# larduino.net
KiCad netlist of a schematic drawn in Altium Designer
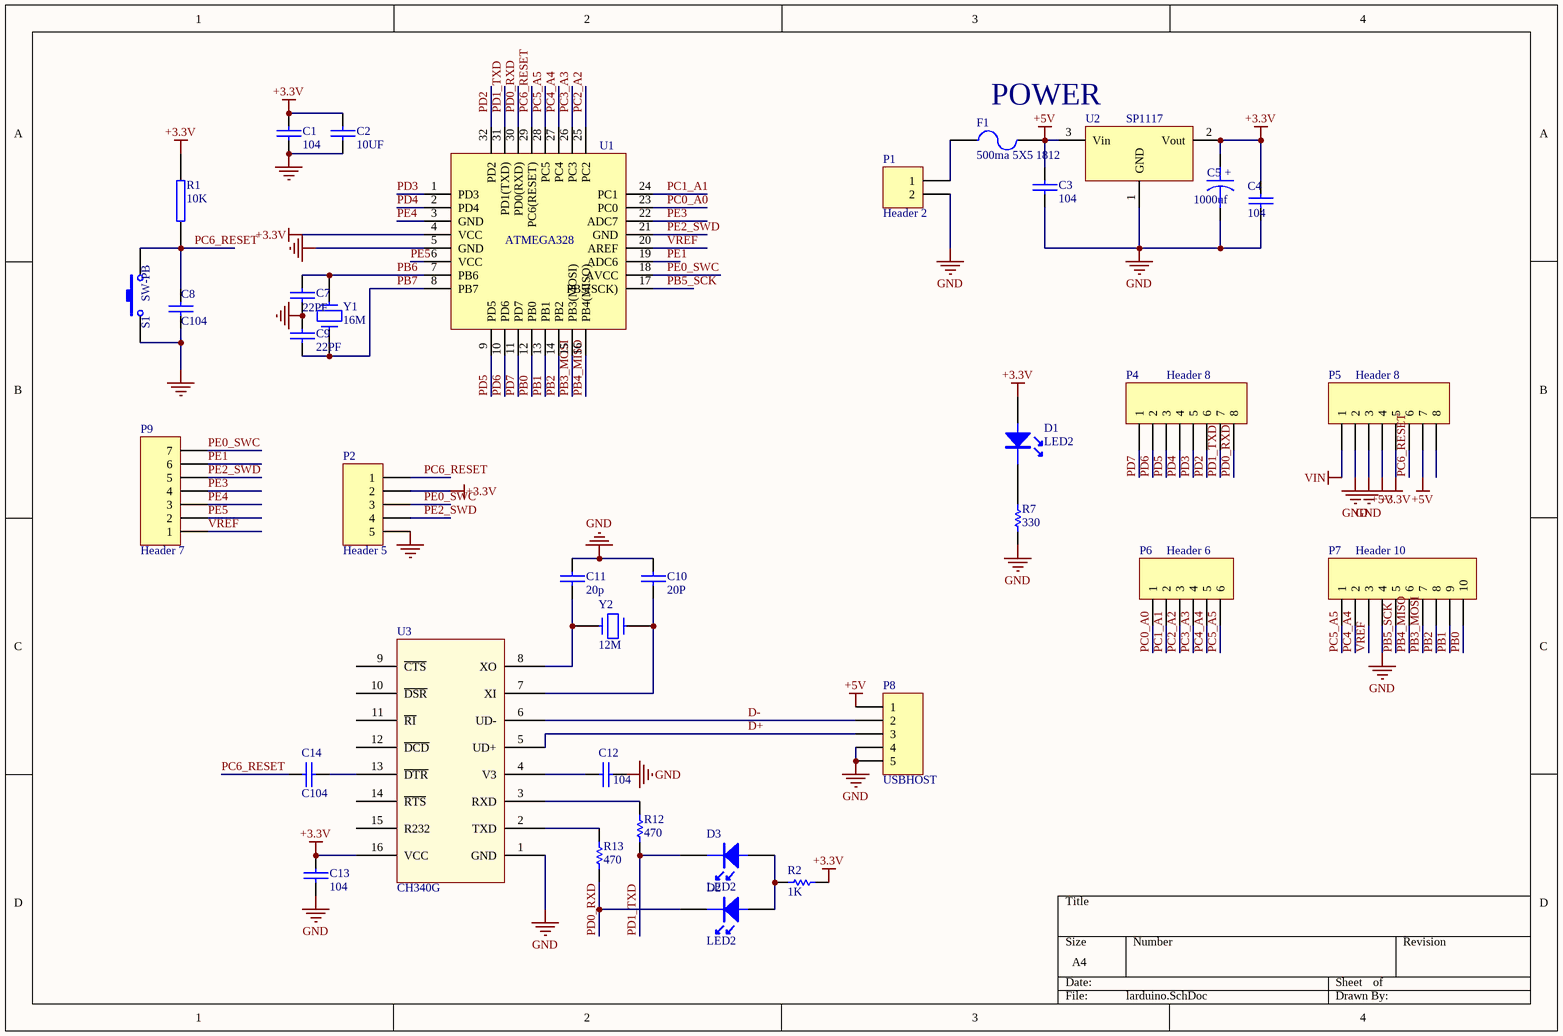
[diagram p0: larduino.SchDoc]

(export (version "E")
  (design (tool "Eeschema 10.0.6"))
  (components
    (comp (ref "C1")
      (value "104")
      (footprint "0805C1")
      (description "Capacitor")
      (libsource (lib "*") (part "CAP"))
    )
    (comp (ref "C2")
      (value "10UF")
      (footprint "0805C1")
      (description "Capacitor")
      (libsource (lib "*") (part "CAP"))
    )
    (comp (ref "C3")
      (value "104")
      (footprint "0805C1")
      (description "Capacitor")
      (libsource (lib "*") (part "CAP"))
    )
    (comp (ref "C4")
      (value "104")
      (footprint "0805C1")
      (description "Capacitor")
      (libsource (lib "*") (part "CAP"))
    )
    (comp (ref "C5")
      (value "1000uf")
      (footprint "c6.3*5.3")
      (description "Capacitor")
      (libsource (lib "*") (part "CAPACITOR POL"))
    )
    (comp (ref "C7")
      (value "22PF")
      (footprint "0805C1")
      (description "Capacitor")
      (libsource (lib "*") (part "CAP"))
    )
    (comp (ref "C8")
      (value "C104")
      (footprint "0805C1")
      (description "Capacitor")
      (libsource (lib "*") (part "CAP"))
    )
    (comp (ref "C9")
      (value "22PF")
      (footprint "0805C1")
      (description "Capacitor")
      (libsource (lib "*") (part "CAP"))
    )
    (comp (ref "C10")
      (value "20P")
      (footprint "0805C1")
      (description "Capacitor")
      (libsource (lib "*") (part "CAP"))
    )
    (comp (ref "C11")
      (value "20p")
      (footprint "0805C1")
      (description "Capacitor")
      (libsource (lib "*") (part "CAP"))
    )
    (comp (ref "C12")
      (value "104")
      (footprint "0805C1")
      (description "Capacitor")
      (libsource (lib "*") (part "CAP"))
    )
    (comp (ref "C13")
      (value "104")
      (footprint "0805C1")
      (description "Capacitor")
      (libsource (lib "*") (part "CAP"))
    )
    (comp (ref "C14")
      (value "C104")
      (footprint "0805C1")
      (description "Capacitor")
      (libsource (lib "*") (part "CAP"))
    )
    (comp (ref "D1") (value "LED2") (footprint "0805LED") (libsource (lib "*") (part "LED")))
    (comp (ref "D2") (value "LED2") (footprint "0805LED") (libsource (lib "*") (part "LED")))
    (comp (ref "D3") (value "LED2") (footprint "0805LED") (libsource (lib "*") (part "LED")))
    (comp (ref "F1")
      (value "500ma 5X5 1812")
      (footprint "1812R")
      (description "Fuse")
      (fields (field (name "PUBLISHER") "Altium Limited"))
      (libsource (lib "Miscellaneous Devices") (part "Fuse 2"))
    )
    (comp (ref "P1")
      (value "Header 2")
      (footprint "5VINPUT")
      (description "Header, 2-Pin")
      (fields (field (name "PUBLISHER") "Altium Limited"))
      (libsource (lib "Miscellaneous Connectors") (part "Header 2"))
    )
    (comp (ref "P2")
      (value "Header 5")
      (footprint "HDR1X5")
      (description "Header, 5-Pin")
      (fields (field (name "PUBLISHER") "Altium Limited"))
      (libsource (lib "") (part "Header 5_1"))
    )
    (comp (ref "P4")
      (value "Header 8")
      (footprint "HDR1X8")
      (description "Header, 8-Pin")
      (fields (field (name "PUBLISHER") "Altium Limited"))
      (libsource (lib "Miscellaneous Connectors") (part "Header 8"))
    )
    (comp (ref "P5")
      (value "Header 8")
      (footprint "HDR1X8")
      (description "Header, 8-Pin")
      (fields (field (name "PUBLISHER") "Altium Limited"))
      (libsource (lib "Miscellaneous Connectors") (part "Header 8"))
    )
    (comp (ref "P6")
      (value "Header 6")
      (footprint "HDR1X6")
      (description "Header, 6-Pin")
      (fields (field (name "PUBLISHER") "Altium Limited"))
      (libsource (lib "Miscellaneous Connectors") (part "Header 6"))
    )
    (comp (ref "P7")
      (value "Header 10")
      (footprint "HDR1X10")
      (description "Header, 10-Pin")
      (fields (field (name "PUBLISHER") "Altium Limited"))
      (libsource (lib "Miscellaneous Connectors") (part "Header 10"))
    )
    (comp (ref "P8")
      (value "USBHOST")
      (footprint "USB_mini")
      (description "Header, 5-Pin")
      (fields (field (name "PUBLISHER") "Altium Limited"))
      (libsource (lib "Miscellaneous Connectors") (part "Header 5"))
    )
    (comp (ref "P9")
      (value "Header 7")
      (footprint "HDR1X7")
      (description "Header, 7-Pin")
      (fields (field (name "PUBLISHER") "Altium Limited"))
      (libsource (lib "Miscellaneous Connectors") (part "Header 7"))
    )
    (comp (ref "R1") (value "10K") (footprint "0805R1") (libsource (lib "*") (part "RES2")))
    (comp (ref "R2")
      (value "1K")
      (footprint "0805R1")
      (description "Semiconductor Resistor")
      (fields (field (name "Comment") "Res Semi") (field (name "PUBLISHER") "Altium Limited"))
      (libsource (lib "Miscellaneous Devices") (part "Res Semi"))
    )
    (comp (ref "R7")
      (value "330")
      (footprint "0805R1")
      (description "Resistor")
      (fields (field (name "Comment") "Res1") (field (name "PUBLISHER") "Altium Limited"))
      (libsource (lib "Miscellaneous Devices") (part "Res1"))
    )
    (comp (ref "R12")
      (value "470")
      (footprint "0805R1")
      (description "Semiconductor Resistor")
      (fields (field (name "Comment") "Res Semi") (field (name "PUBLISHER") "Altium Limited"))
      (libsource (lib "Miscellaneous Devices") (part "Res Semi"))
    )
    (comp (ref "R13")
      (value "470")
      (footprint "0805R1")
      (description "Semiconductor Resistor")
      (fields (field (name "Comment") "Res Semi") (field (name "PUBLISHER") "Altium Limited"))
      (libsource (lib "Miscellaneous Devices") (part "Res Semi"))
    )
    (comp (ref "S1")
      (value "SW-PB")
      (footprint "KEY_6*6*X _SMT")
      (description "Switch")
      (fields (field (name "PUBLISHER") "Altium Limited"))
      (libsource (lib "Miscellaneous Devices") (part "SW-PB"))
    )
    (comp (ref "U1") (value "ATMEGA328") (footprint "TQFP32") (libsource (lib "*") (part "ATMEAG328")))
    (comp (ref "U2") (value "SP1117") (footprint "SOT-223") (libsource (lib "hhregulator") (part "SP1117")))
    (comp (ref "U3") (value "CH340G") (footprint "SO-16") (libsource (lib "hhic") (part "CH340G")))
    (comp (ref "Y1")
      (value "16M")
      (footprint "XTAL_smd1")
      (description "Crystal")
      (libsource (lib "*") (part "CRYSTAL"))
    )
    (comp (ref "Y2")
      (value "12M")
      (footprint "XTAL_smd1")
      (description "Crystal")
      (libsource (lib "*") (part "CRYSTAL"))
    )
  )
  (nets
    (net (code "1") (name "+3.3V") (class "Default")
      (node (ref "C1") (pin "1") (pinfunction "1_1") (pintype "passive"))
      (node (ref "C13") (pin "2") (pinfunction "2_2") (pintype "passive"))
      (node (ref "C2") (pin "1") (pinfunction "1_1") (pintype "passive"))
      (node (ref "C4") (pin "1") (pinfunction "1_1") (pintype "passive"))
      (node (ref "C5") (pin "1") (pinfunction "1_1") (pintype "passive"))
      (node (ref "D1") (pin "1") (pinfunction "1_1") (pintype "passive"))
      (node (ref "P2") (pin "2") (pinfunction "2_2") (pintype "passive"))
      (node (ref "P5") (pin "5") (pinfunction "5_5") (pintype "passive"))
      (node (ref "R1") (pin "1") (pinfunction "1_1") (pintype "passive"))
      (node (ref "R2") (pin "2") (pinfunction "2_2") (pintype "passive"))
      (node (ref "U1") (pin "4") (pinfunction "VCC_4") (pintype "passive"))
      (node (ref "U2") (pin "2") (pinfunction "Vout_2") (pintype "passive"))
      (node (ref "U3") (pin "16") (pinfunction "VCC_16") (pintype "passive"))
    )
    (net (code "2") (name "+5V") (class "Default")
      (node (ref "C3") (pin "2") (pinfunction "2_2") (pintype "passive"))
      (node (ref "F1") (pin "2") (pinfunction "2_2") (pintype "passive"))
      (node (ref "P5") (pin "4") (pinfunction "4_4") (pintype "passive"))
      (node (ref "P5") (pin "7") (pinfunction "7_7") (pintype "passive"))
      (node (ref "P8") (pin "1") (pinfunction "1_1") (pintype "passive"))
      (node (ref "U2") (pin "3") (pinfunction "Vin_3") (pintype "passive"))
    )
    (net (code "3") (name "/D+") (class "Default")
      (node (ref "P8") (pin "3") (pinfunction "3_3") (pintype "passive"))
      (node (ref "U3") (pin "5") (pinfunction "UD+_5") (pintype "passive"))
    )
    (net (code "4") (name "/D-") (class "Default")
      (node (ref "P8") (pin "2") (pinfunction "2_2") (pintype "passive"))
      (node (ref "U3") (pin "6") (pinfunction "UD-_6") (pintype "passive"))
    )
    (net (code "5") (name "/PB0") (class "Default")
      (node (ref "P7") (pin "10") (pinfunction "10_10") (pintype "passive"))
      (node (ref "U1") (pin "12") (pinfunction "PB0_12") (pintype "passive"))
    )
    (net (code "6") (name "/PB1") (class "Default")
      (node (ref "P7") (pin "9") (pinfunction "9_9") (pintype "passive"))
      (node (ref "U1") (pin "13") (pinfunction "PB1_13") (pintype "passive"))
    )
    (net (code "7") (name "/PB2") (class "Default")
      (node (ref "P7") (pin "8") (pinfunction "8_8") (pintype "passive"))
      (node (ref "U1") (pin "14") (pinfunction "PB2_14") (pintype "passive"))
    )
    (net (code "8") (name "/PB3_MOSI") (class "Default")
      (node (ref "P7") (pin "7") (pinfunction "7_7") (pintype "passive"))
      (node (ref "U1") (pin "15") (pinfunction "PB3(MOSI)_15") (pintype "passive"))
    )
    (net (code "9") (name "/PB4_MISO") (class "Default")
      (node (ref "P7") (pin "6") (pinfunction "6_6") (pintype "passive"))
      (node (ref "U1") (pin "16") (pinfunction "PB4(MISO)_16") (pintype "passive"))
    )
    (net (code "10") (name "/PB5_SCK") (class "Default")
      (node (ref "P7") (pin "5") (pinfunction "5_5") (pintype "passive"))
      (node (ref "U1") (pin "17") (pinfunction "PB5(SCK)_17") (pintype "passive"))
    )
    (net (code "11") (name "/PB6") (class "Default")
      (node (ref "C7") (pin "1") (pinfunction "1_1") (pintype "passive"))
      (node (ref "U1") (pin "7") (pinfunction "PB6_7") (pintype "passive"))
      (node (ref "Y1") (pin "1") (pinfunction "1_1") (pintype "passive"))
    )
    (net (code "12") (name "/PB7") (class "Default")
      (node (ref "C9") (pin "2") (pinfunction "2_2") (pintype "passive"))
      (node (ref "U1") (pin "8") (pinfunction "PB7_8") (pintype "passive"))
      (node (ref "Y1") (pin "2") (pinfunction "2_2") (pintype "passive"))
    )
    (net (code "13") (name "/PC0_A0") (class "Default")
      (node (ref "P6") (pin "1") (pinfunction "1_1") (pintype "passive"))
      (node (ref "U1") (pin "23") (pinfunction "PC0_23") (pintype "passive"))
    )
    (net (code "14") (name "/PC1_A1") (class "Default")
      (node (ref "P6") (pin "2") (pinfunction "2_2") (pintype "passive"))
      (node (ref "U1") (pin "24") (pinfunction "PC1_24") (pintype "passive"))
    )
    (net (code "15") (name "/PC2_A2") (class "Default")
      (node (ref "P6") (pin "3") (pinfunction "3_3") (pintype "passive"))
      (node (ref "U1") (pin "25") (pinfunction "PC2_25") (pintype "passive"))
    )
    (net (code "16") (name "/PC3_A3") (class "Default")
      (node (ref "P6") (pin "4") (pinfunction "4_4") (pintype "passive"))
      (node (ref "U1") (pin "26") (pinfunction "PC3_26") (pintype "passive"))
    )
    (net (code "17") (name "/PC4_A4") (class "Default")
      (node (ref "P6") (pin "5") (pinfunction "5_5") (pintype "passive"))
      (node (ref "P7") (pin "2") (pinfunction "2_2") (pintype "passive"))
      (node (ref "U1") (pin "27") (pinfunction "PC4_27") (pintype "passive"))
    )
    (net (code "18") (name "/PC5_A5") (class "Default")
      (node (ref "P6") (pin "6") (pinfunction "6_6") (pintype "passive"))
      (node (ref "P7") (pin "1") (pinfunction "1_1") (pintype "passive"))
      (node (ref "U1") (pin "28") (pinfunction "PC5_28") (pintype "passive"))
    )
    (net (code "19") (name "/PC6_RESET") (class "Default")
      (node (ref "C14") (pin "1") (pinfunction "1_1") (pintype "passive"))
      (node (ref "C8") (pin "1") (pinfunction "1_1") (pintype "passive"))
      (node (ref "P2") (pin "1") (pinfunction "1_1") (pintype "passive"))
      (node (ref "P5") (pin "6") (pinfunction "6_6") (pintype "passive"))
      (node (ref "R1") (pin "2") (pinfunction "2_2") (pintype "passive"))
      (node (ref "S1") (pin "1") (pinfunction "1_1") (pintype "passive"))
      (node (ref "U1") (pin "29") (pinfunction "PC6(RESET)_29") (pintype "passive"))
    )
    (net (code "20") (name "/PD0_RXD") (class "Default")
      (node (ref "D2") (pin "2") (pinfunction "2_2") (pintype "passive"))
      (node (ref "P4") (pin "8") (pinfunction "8_8") (pintype "passive"))
      (node (ref "R13") (pin "2") (pinfunction "2_2") (pintype "passive"))
      (node (ref "U1") (pin "30") (pinfunction "PD0(RXD)_30") (pintype "passive"))
    )
    (net (code "21") (name "/PD1_TXD") (class "Default")
      (node (ref "D3") (pin "2") (pinfunction "2_2") (pintype "passive"))
      (node (ref "P4") (pin "7") (pinfunction "7_7") (pintype "passive"))
      (node (ref "R12") (pin "2") (pinfunction "2_2") (pintype "passive"))
      (node (ref "U1") (pin "31") (pinfunction "PD1(TXD)_31") (pintype "passive"))
    )
    (net (code "22") (name "/PD2") (class "Default")
      (node (ref "P4") (pin "6") (pinfunction "6_6") (pintype "passive"))
      (node (ref "U1") (pin "32") (pinfunction "PD2_32") (pintype "passive"))
    )
    (net (code "23") (name "/PD3") (class "Default")
      (node (ref "P4") (pin "5") (pinfunction "5_5") (pintype "passive"))
      (node (ref "U1") (pin "1") (pinfunction "PD3_1") (pintype "passive"))
    )
    (net (code "24") (name "/PD4") (class "Default")
      (node (ref "P4") (pin "4") (pinfunction "4_4") (pintype "passive"))
      (node (ref "U1") (pin "2") (pinfunction "PD4_2") (pintype "passive"))
    )
    (net (code "25") (name "/PD5") (class "Default")
      (node (ref "P4") (pin "3") (pinfunction "3_3") (pintype "passive"))
      (node (ref "U1") (pin "9") (pinfunction "PD5_9") (pintype "passive"))
    )
    (net (code "26") (name "/PD6") (class "Default")
      (node (ref "P4") (pin "2") (pinfunction "2_2") (pintype "passive"))
      (node (ref "U1") (pin "10") (pinfunction "PD6_10") (pintype "passive"))
    )
    (net (code "27") (name "/PD7") (class "Default")
      (node (ref "P4") (pin "1") (pinfunction "1_1") (pintype "passive"))
      (node (ref "U1") (pin "11") (pinfunction "PD7_11") (pintype "passive"))
    )
    (net (code "28") (name "/PE0_SWC") (class "Default")
      (node (ref "P2") (pin "3") (pinfunction "3_3") (pintype "passive"))
      (node (ref "P9") (pin "7") (pinfunction "7_7") (pintype "passive"))
      (node (ref "U1") (pin "18") (pinfunction "AVCC_18") (pintype "passive"))
    )
    (net (code "29") (name "/PE1") (class "Default")
      (node (ref "P9") (pin "6") (pinfunction "6_6") (pintype "passive"))
      (node (ref "U1") (pin "19") (pinfunction "ADC6_19") (pintype "passive"))
    )
    (net (code "30") (name "/PE2_SWD") (class "Default")
      (node (ref "P2") (pin "4") (pinfunction "4_4") (pintype "passive"))
      (node (ref "P9") (pin "5") (pinfunction "5_5") (pintype "passive"))
      (node (ref "U1") (pin "21") (pinfunction "GND_21") (pintype "passive"))
    )
    (net (code "31") (name "/PE3") (class "Default")
      (node (ref "P9") (pin "4") (pinfunction "4_4") (pintype "passive"))
      (node (ref "U1") (pin "22") (pinfunction "ADC7_22") (pintype "passive"))
    )
    (net (code "32") (name "/PE4") (class "Default")
      (node (ref "P9") (pin "3") (pinfunction "3_3") (pintype "passive"))
      (node (ref "U1") (pin "3") (pinfunction "GND_3") (pintype "passive"))
    )
    (net (code "33") (name "/PE5") (class "Default")
      (node (ref "P9") (pin "2") (pinfunction "2_2") (pintype "passive"))
      (node (ref "U1") (pin "6") (pinfunction "VCC_6") (pintype "passive"))
    )
    (net (code "34") (name "/VREF") (class "Default")
      (node (ref "P7") (pin "3") (pinfunction "3_3") (pintype "passive"))
      (node (ref "P9") (pin "1") (pinfunction "1_1") (pintype "passive"))
      (node (ref "U1") (pin "20") (pinfunction "AREF_20") (pintype "passive"))
    )
    (net (code "35") (name "GND") (class "Default")
      (node (ref "C1") (pin "2") (pinfunction "2_2") (pintype "passive"))
      (node (ref "C10") (pin "2") (pinfunction "2_2") (pintype "passive"))
      (node (ref "C11") (pin "2") (pinfunction "2_2") (pintype "passive"))
      (node (ref "C12") (pin "1") (pinfunction "1_1") (pintype "passive"))
      (node (ref "C13") (pin "1") (pinfunction "1_1") (pintype "passive"))
      (node (ref "C2") (pin "2") (pinfunction "2_2") (pintype "passive"))
      (node (ref "C3") (pin "1") (pinfunction "1_1") (pintype "passive"))
      (node (ref "C4") (pin "2") (pinfunction "2_2") (pintype "passive"))
      (node (ref "C5") (pin "2") (pinfunction "2_2") (pintype "passive"))
      (node (ref "C7") (pin "2") (pinfunction "2_2") (pintype "passive"))
      (node (ref "C8") (pin "2") (pinfunction "2_2") (pintype "passive"))
      (node (ref "C9") (pin "1") (pinfunction "1_1") (pintype "passive"))
      (node (ref "P1") (pin "2") (pinfunction "2_2") (pintype "passive"))
      (node (ref "P2") (pin "5") (pinfunction "5_5") (pintype "passive"))
      (node (ref "P5") (pin "2") (pinfunction "2_2") (pintype "passive"))
      (node (ref "P5") (pin "3") (pinfunction "3_3") (pintype "passive"))
      (node (ref "P7") (pin "4") (pinfunction "4_4") (pintype "passive"))
      (node (ref "P8") (pin "4") (pinfunction "4_4") (pintype "passive"))
      (node (ref "P8") (pin "5") (pinfunction "5_5") (pintype "passive"))
      (node (ref "R7") (pin "2") (pinfunction "2_2") (pintype "passive"))
      (node (ref "S1") (pin "2") (pinfunction "2_2") (pintype "passive"))
      (node (ref "U1") (pin "5") (pinfunction "GND_5") (pintype "passive"))
      (node (ref "U2") (pin "1") (pinfunction "GND_1") (pintype "passive"))
      (node (ref "U3") (pin "1") (pinfunction "GND_1") (pintype "passive"))
    )
    (net (code "36") (name "Net-(D1-Pad2)") (class "Default")
      (node (ref "D1") (pin "2") (pinfunction "2_2") (pintype "passive"))
      (node (ref "R7") (pin "1") (pinfunction "1_1") (pintype "passive"))
    )
    (net (code "37") (name "Net-(D2-Pad1)") (class "Default")
      (node (ref "D2") (pin "1") (pinfunction "1_1") (pintype "passive"))
      (node (ref "D3") (pin "1") (pinfunction "1_1") (pintype "passive"))
      (node (ref "R2") (pin "1") (pinfunction "1_1") (pintype "passive"))
    )
    (net (code "38") (name "Net-(F1-Pad1)") (class "Default")
      (node (ref "F1") (pin "1") (pinfunction "1_1") (pintype "passive"))
      (node (ref "P1") (pin "1") (pinfunction "1_1") (pintype "passive"))
    )
    (net (code "39") (name "Net-(U3-RXD)") (class "Default")
      (node (ref "R12") (pin "1") (pinfunction "1_1") (pintype "passive"))
      (node (ref "U3") (pin "3") (pinfunction "RXD_3") (pintype "passive"))
    )
    (net (code "40") (name "Net-(U3-TXD)") (class "Default")
      (node (ref "R13") (pin "1") (pinfunction "1_1") (pintype "passive"))
      (node (ref "U3") (pin "2") (pinfunction "TXD_2") (pintype "passive"))
    )
    (net (code "41") (name "Net-(U3-V3)") (class "Default")
      (node (ref "C12") (pin "2") (pinfunction "2_2") (pintype "passive"))
      (node (ref "U3") (pin "4") (pinfunction "V3_4") (pintype "passive"))
    )
    (net (code "42") (name "Net-(U3-XI)") (class "Default")
      (node (ref "C10") (pin "1") (pinfunction "1_1") (pintype "passive"))
      (node (ref "U3") (pin "7") (pinfunction "XI_7") (pintype "passive"))
      (node (ref "Y2") (pin "1") (pinfunction "1_1") (pintype "passive"))
    )
    (net (code "43") (name "Net-(U3-XO)") (class "Default")
      (node (ref "C11") (pin "1") (pinfunction "1_1") (pintype "passive"))
      (node (ref "U3") (pin "8") (pinfunction "XO_8") (pintype "passive"))
      (node (ref "Y2") (pin "2") (pinfunction "2_2") (pintype "passive"))
    )
    (net (code "44") (name "Net-(U3-~{DTR})") (class "Default")
      (node (ref "C14") (pin "2") (pinfunction "2_2") (pintype "passive"))
      (node (ref "U3") (pin "13") (pinfunction "~{DTR}_13") (pintype "passive"))
    )
    (net (code "45") (name "VIN") (class "Default")
      (node (ref "P5") (pin "1") (pinfunction "1_1") (pintype "passive"))
    )
    (net (code "46") (name "unconnected-(P5-Pad8)") (class "Default")
      (node (ref "P5") (pin "8") (pinfunction "8_8") (pintype "passive"))
    )
    (net (code "47") (name "unconnected-(U3-R232-Pad15)") (class "Default")
      (node (ref "U3") (pin "15") (pinfunction "R232_15") (pintype "passive"))
    )
    (net (code "48") (name "unconnected-(U3-~{CTS}-Pad9)") (class "Default")
      (node (ref "U3") (pin "9") (pinfunction "~{CTS}_9") (pintype "passive"))
    )
    (net (code "49") (name "unconnected-(U3-~{DCD}-Pad12)") (class "Default")
      (node (ref "U3") (pin "12") (pinfunction "~{DCD}_12") (pintype "passive"))
    )
    (net (code "50") (name "unconnected-(U3-~{DSR}-Pad10)") (class "Default")
      (node (ref "U3") (pin "10") (pinfunction "~{DSR}_10") (pintype "passive"))
    )
    (net (code "51") (name "unconnected-(U3-~{RI}-Pad11)") (class "Default")
      (node (ref "U3") (pin "11") (pinfunction "~{RI}_11") (pintype "passive"))
    )
    (net (code "52") (name "unconnected-(U3-~{RTS}-Pad14)") (class "Default")
      (node (ref "U3") (pin "14") (pinfunction "~{RTS}_14") (pintype "passive"))
    )
  )
)
